# AT90CAN128.net
KiCad netlist of a schematic drawn in Altium Designer
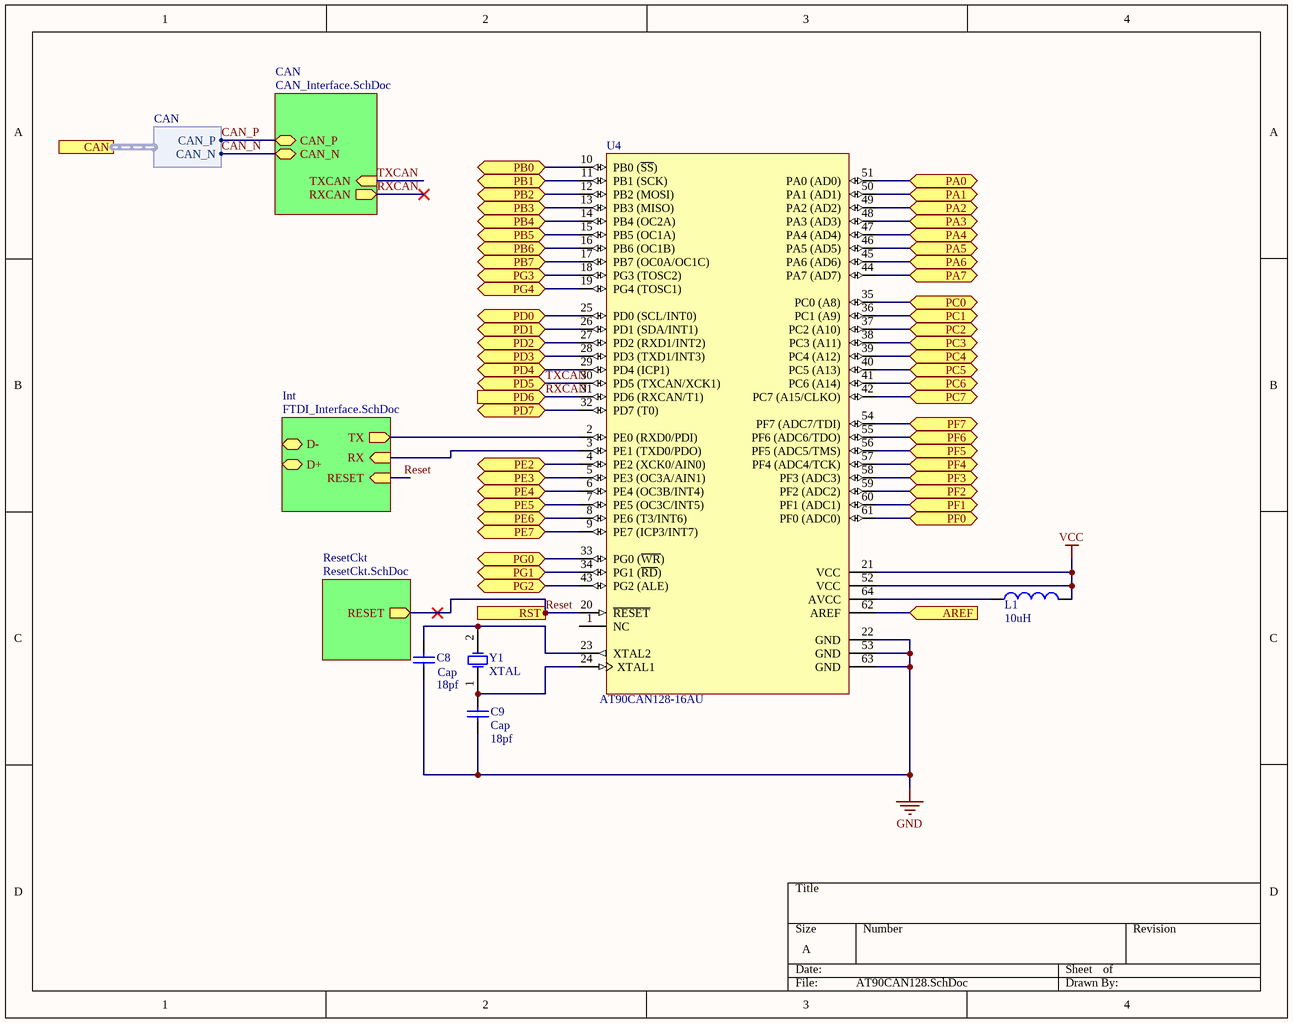
[diagram p0: AT90CAN128.SchDoc]

(export (version "E")
  (design (tool "Eeschema 10.0.6"))
  (components
    (comp (ref "C8")
      (value "Cap")
      (footprint "C0805")
      (description "Capacitor")
      (fields (field (name "ALTIUM_VALUE") "18pf") (field (name "PUBLISHER") "Altium Limited"))
      (libsource (lib "Miscellaneous Devices") (part "Cap"))
    )
    (comp (ref "C9")
      (value "Cap")
      (footprint "C0805")
      (description "Capacitor")
      (fields (field (name "ALTIUM_VALUE") "18pf") (field (name "PUBLISHER") "Altium Limited"))
      (libsource (lib "Miscellaneous Devices") (part "Cap"))
    )
    (comp (ref "L1")
      (value "10uH")
      (footprint "INDC3216")
      (description "Inductor")
      (fields (field (name "PUBLISHER") "Altium Limited"))
      (libsource (lib "Miscellaneous Devices") (part "Inductor"))
    )
    (comp (ref "U4")
      (value "AT90CAN128-16AU")
      (footprint "64A_M")
      (libsource (lib "Altium Content Vault") (part "MC-8B-AT90CAN32-SQ64"))
    )
    (comp (ref "Y1")
      (value "XTAL")
      (footprint "6-0805_L")
      (description "Crystal Oscillator")
      (fields (field (name "PUBLISHER") "Altium Limited"))
      (libsource (lib "Miscellaneous Devices") (part "XTAL"))
    )
  )
  (nets
    (net (code "2") (name "/AREF") (class "Default")
      (node (ref "U4") (pin "62") (pinfunction "AREF_62") (pintype "power_in"))
    )
    (net (code "7") (name "/PA0") (class "Default")
      (node (ref "U4") (pin "51") (pinfunction "PA0_(AD0)_51") (pintype "bidirectional"))
    )
    (net (code "8") (name "/PA1") (class "Default")
      (node (ref "U4") (pin "50") (pinfunction "PA1_(AD1)_50") (pintype "bidirectional"))
    )
    (net (code "9") (name "/PA2") (class "Default")
      (node (ref "U4") (pin "49") (pinfunction "PA2_(AD2)_49") (pintype "bidirectional"))
    )
    (net (code "10") (name "/PA3") (class "Default")
      (node (ref "U4") (pin "48") (pinfunction "PA3_(AD3)_48") (pintype "bidirectional"))
    )
    (net (code "11") (name "/PA4") (class "Default")
      (node (ref "U4") (pin "47") (pinfunction "PA4_(AD4)_47") (pintype "bidirectional"))
    )
    (net (code "12") (name "/PA5") (class "Default")
      (node (ref "U4") (pin "46") (pinfunction "PA5_(AD5)_46") (pintype "bidirectional"))
    )
    (net (code "13") (name "/PA6") (class "Default")
      (node (ref "U4") (pin "45") (pinfunction "PA6_(AD6)_45") (pintype "bidirectional"))
    )
    (net (code "14") (name "/PA7") (class "Default")
      (node (ref "U4") (pin "44") (pinfunction "PA7_(AD7)_44") (pintype "bidirectional"))
    )
    (net (code "15") (name "/PB0") (class "Default")
      (node (ref "U4") (pin "10") (pinfunction "PB0_(~{SS})_10") (pintype "bidirectional"))
    )
    (net (code "16") (name "/PB1") (class "Default")
      (node (ref "U4") (pin "11") (pinfunction "PB1_(SCK)_11") (pintype "bidirectional"))
    )
    (net (code "17") (name "/PB2") (class "Default")
      (node (ref "U4") (pin "12") (pinfunction "PB2_(MOSI)_12") (pintype "bidirectional"))
    )
    (net (code "18") (name "/PB3") (class "Default")
      (node (ref "U4") (pin "13") (pinfunction "PB3_(MISO)_13") (pintype "bidirectional"))
    )
    (net (code "19") (name "/PB4") (class "Default")
      (node (ref "U4") (pin "14") (pinfunction "PB4_(OC2A)_14") (pintype "bidirectional"))
    )
    (net (code "20") (name "/PB5") (class "Default")
      (node (ref "U4") (pin "15") (pinfunction "PB5_(OC1A)_15") (pintype "bidirectional"))
    )
    (net (code "21") (name "/PB6") (class "Default")
      (node (ref "U4") (pin "16") (pinfunction "PB6_(OC1B)_16") (pintype "bidirectional"))
    )
    (net (code "22") (name "/PB7") (class "Default")
      (node (ref "U4") (pin "17") (pinfunction "PB7_(OC0A/OC1C)_17") (pintype "bidirectional"))
    )
    (net (code "23") (name "/PC0") (class "Default")
      (node (ref "U4") (pin "35") (pinfunction "PC0_(A8)_35") (pintype "bidirectional"))
    )
    (net (code "24") (name "/PC1") (class "Default")
      (node (ref "U4") (pin "36") (pinfunction "PC1_(A9)_36") (pintype "bidirectional"))
    )
    (net (code "25") (name "/PC2") (class "Default")
      (node (ref "U4") (pin "37") (pinfunction "PC2_(A10)_37") (pintype "bidirectional"))
    )
    (net (code "26") (name "/PC3") (class "Default")
      (node (ref "U4") (pin "38") (pinfunction "PC3_(A11)_38") (pintype "bidirectional"))
    )
    (net (code "27") (name "/PC4") (class "Default")
      (node (ref "U4") (pin "39") (pinfunction "PC4_(A12)_39") (pintype "bidirectional"))
    )
    (net (code "28") (name "/PC5") (class "Default")
      (node (ref "U4") (pin "40") (pinfunction "PC5_(A13)_40") (pintype "bidirectional"))
    )
    (net (code "29") (name "/PC6") (class "Default")
      (node (ref "U4") (pin "41") (pinfunction "PC6_(A14)_41") (pintype "bidirectional"))
    )
    (net (code "30") (name "/PC7") (class "Default")
      (node (ref "U4") (pin "42") (pinfunction "PC7_(A15/CLKO)_42") (pintype "bidirectional"))
    )
    (net (code "31") (name "/PD0") (class "Default")
      (node (ref "U4") (pin "25") (pinfunction "PD0_(SCL/INT0)_25") (pintype "bidirectional"))
    )
    (net (code "32") (name "/PD1") (class "Default")
      (node (ref "U4") (pin "26") (pinfunction "PD1_(SDA/INT1)_26") (pintype "bidirectional"))
    )
    (net (code "33") (name "/PD2") (class "Default")
      (node (ref "U4") (pin "27") (pinfunction "PD2_(RXD1/INT2)_27") (pintype "bidirectional"))
    )
    (net (code "34") (name "/PD3") (class "Default")
      (node (ref "U4") (pin "28") (pinfunction "PD3_(TXD1/INT3)_28") (pintype "bidirectional"))
    )
    (net (code "35") (name "/PD4") (class "Default")
      (node (ref "U4") (pin "29") (pinfunction "PD4_(ICP1)_29") (pintype "bidirectional"))
    )
    (net (code "36") (name "/PD7") (class "Default")
      (node (ref "U4") (pin "32") (pinfunction "PD7_(T0)_32") (pintype "bidirectional"))
    )
    (net (code "37") (name "/PE2") (class "Default")
      (node (ref "U4") (pin "4") (pinfunction "PE2_(XCK0/AIN0)_4") (pintype "bidirectional"))
    )
    (net (code "38") (name "/PE3") (class "Default")
      (node (ref "U4") (pin "5") (pinfunction "PE3_(OC3A/AIN1)_5") (pintype "bidirectional"))
    )
    (net (code "39") (name "/PE4") (class "Default")
      (node (ref "U4") (pin "6") (pinfunction "PE4_(OC3B/INT4)_6") (pintype "bidirectional"))
    )
    (net (code "40") (name "/PE5") (class "Default")
      (node (ref "U4") (pin "7") (pinfunction "PE5_(OC3C/INT5)_7") (pintype "bidirectional"))
    )
    (net (code "41") (name "/PE6") (class "Default")
      (node (ref "U4") (pin "8") (pinfunction "PE6_(T3/INT6)_8") (pintype "bidirectional"))
    )
    (net (code "42") (name "/PE7") (class "Default")
      (node (ref "U4") (pin "9") (pinfunction "PE7_(ICP3/INT7)_9") (pintype "bidirectional"))
    )
    (net (code "43") (name "/PF0") (class "Default")
      (node (ref "U4") (pin "61") (pinfunction "PF0_(ADC0)_61") (pintype "bidirectional"))
    )
    (net (code "44") (name "/PF1") (class "Default")
      (node (ref "U4") (pin "60") (pinfunction "PF1_(ADC1)_60") (pintype "bidirectional"))
    )
    (net (code "45") (name "/PF2") (class "Default")
      (node (ref "U4") (pin "59") (pinfunction "PF2_(ADC2)_59") (pintype "bidirectional"))
    )
    (net (code "46") (name "/PF3") (class "Default")
      (node (ref "U4") (pin "58") (pinfunction "PF3_(ADC3)_58") (pintype "bidirectional"))
    )
    (net (code "47") (name "/PF4") (class "Default")
      (node (ref "U4") (pin "57") (pinfunction "PF4_(ADC4/TCK)_57") (pintype "bidirectional"))
    )
    (net (code "48") (name "/PF5") (class "Default")
      (node (ref "U4") (pin "56") (pinfunction "PF5_(ADC5/TMS)_56") (pintype "bidirectional"))
    )
    (net (code "49") (name "/PF6") (class "Default")
      (node (ref "U4") (pin "55") (pinfunction "PF6_(ADC6/TDO)_55") (pintype "bidirectional"))
    )
    (net (code "50") (name "/PF7") (class "Default")
      (node (ref "U4") (pin "54") (pinfunction "PF7_(ADC7/TDI)_54") (pintype "bidirectional"))
    )
    (net (code "51") (name "/PG0") (class "Default")
      (node (ref "U4") (pin "33") (pinfunction "PG0_(~{WR})_33") (pintype "bidirectional"))
    )
    (net (code "52") (name "/PG1") (class "Default")
      (node (ref "U4") (pin "34") (pinfunction "PG1_(~{RD})_34") (pintype "bidirectional"))
    )
    (net (code "53") (name "/PG2") (class "Default")
      (node (ref "U4") (pin "43") (pinfunction "PG2_(ALE)_43") (pintype "bidirectional"))
    )
    (net (code "54") (name "/PG3") (class "Default")
      (node (ref "U4") (pin "18") (pinfunction "PG3_(TOSC2)_18") (pintype "bidirectional"))
    )
    (net (code "55") (name "/PG4") (class "Default")
      (node (ref "U4") (pin "19") (pinfunction "PG4_(TOSC1)_19") (pintype "bidirectional"))
    )
    (net (code "56") (name "/RX") (class "Default")
      (node (ref "U4") (pin "3") (pinfunction "PE1_(TXD0/PDO)_3") (pintype "bidirectional"))
    )
    (net (code "57") (name "/RXCAN") (class "Default")
      (node (ref "U4") (pin "31") (pinfunction "PD6_(RXCAN/T1)_31") (pintype "bidirectional+no_connect"))
    )
    (net (code "58") (name "/Reset") (class "Default")
      (node (ref "U4") (pin "20") (pinfunction "~{RESET}_20") (pintype "input"))
    )
    (net (code "59") (name "/TX") (class "Default")
      (node (ref "U4") (pin "2") (pinfunction "PE0_(RXD0/PDI)_2") (pintype "bidirectional"))
    )
    (net (code "60") (name "/TXCAN") (class "Default")
      (node (ref "U4") (pin "30") (pinfunction "PD5_(TXCAN/XCK1)_30") (pintype "bidirectional"))
    )
    (net (code "62") (name "GND") (class "Default")
      (node (ref "C8") (pin "1") (pinfunction "1_1") (pintype "passive"))
      (node (ref "C9") (pin "1") (pinfunction "1_1") (pintype "passive"))
      (node (ref "U4") (pin "22") (pinfunction "GND_22") (pintype "power_in"))
      (node (ref "U4") (pin "53") (pinfunction "GND_53") (pintype "power_in"))
      (node (ref "U4") (pin "63") (pinfunction "GND_63") (pintype "power_in"))
    )
    (net (code "63") (name "Net-(U4-AVCC)") (class "Default")
      (node (ref "L1") (pin "1") (pinfunction "1_1") (pintype "passive"))
      (node (ref "U4") (pin "64") (pinfunction "AVCC_64") (pintype "power_in"))
    )
    (net (code "64") (name "Net-(U4-XTAL1)") (class "Default")
      (node (ref "C9") (pin "2") (pinfunction "2_2") (pintype "passive"))
      (node (ref "U4") (pin "24") (pinfunction "XTAL1_24") (pintype "input"))
      (node (ref "Y1") (pin "1") (pinfunction "OSC1_1") (pintype "passive"))
    )
    (net (code "65") (name "Net-(U4-XTAL2)") (class "Default")
      (node (ref "C8") (pin "2") (pinfunction "2_2") (pintype "passive"))
      (node (ref "U4") (pin "23") (pinfunction "XTAL2_23") (pintype "output"))
      (node (ref "Y1") (pin "2") (pinfunction "OSC2_2") (pintype "passive"))
    )
    (net (code "66") (name "VCC") (class "Default")
      (node (ref "L1") (pin "2") (pinfunction "2_2") (pintype "passive"))
      (node (ref "U4") (pin "21") (pinfunction "VCC_21") (pintype "power_in"))
      (node (ref "U4") (pin "52") (pinfunction "VCC_52") (pintype "power_in"))
    )
    (net (code "67") (name "unconnected-(U4-NC-Pad1)") (class "Default")
      (node (ref "U4") (pin "1") (pinfunction "NC_1") (pintype "passive"))
    )
  )
)
